# indicator_leds.net
KiCad netlist of a schematic drawn in Altium Designer
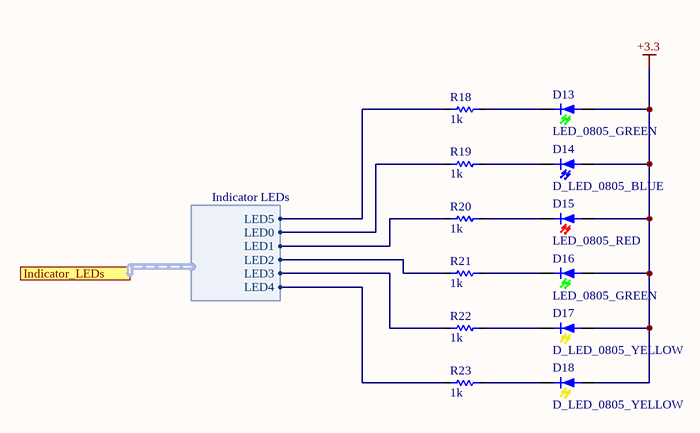
[diagram p0: indicator_leds.SchDoc]

(export (version "E")
  (design (tool "Eeschema 10.0.6"))
  (components
    (comp (ref "D13")
      (value "LED_0805_GREEN")
      (footprint "0805_LED_Green")
      (description "LED CHIPLED 570NM GREEN 0805 SMD")
      (fields
        (field (name "MANUFACTURER") "Osram Opto Semiconductors Inc")
        (field (name "SVP CREATOR") "Nate Bolyard")
      )
      (libsource (lib "University of Minnesota - Solar Vehicle Project") (part "Symbol"))
    )
    (comp (ref "D14")
      (value "D_LED_0805_BLUE")
      (footprint "0805_LED_Blue")
      (description "LED 2X1.2MM 470NM BL WTR CLR SMD")
      (fields (field (name "MANUFACTURER") "Kingbright") (field (name "SVP CREATOR") "Jonathan Nutzmann"))
      (libsource (lib "University of Minnesota - Solar Vehicle Project") (part "Symbol"))
    )
    (comp (ref "D15")
      (value "LED_0805_RED")
      (footprint "0805_LED_Red")
      (description "LED CHIPLED 645NM RED DIFF 0805")
      (fields
        (field (name "MANUFACTURER") "OSRAM Opto Semiconductors Inc")
        (field (name "SVP CREATOR") "Jonathan Nutzmann")
      )
      (libsource (lib "University of Minnesota - Solar Vehicle Project") (part "Symbol"))
    )
    (comp (ref "D16")
      (value "LED_0805_GREEN")
      (footprint "0805_LED_Green")
      (description "LED CHIPLED 570NM GREEN 0805 SMD")
      (fields
        (field (name "MANUFACTURER") "Osram Opto Semiconductors Inc")
        (field (name "SVP CREATOR") "Nate Bolyard")
      )
      (libsource (lib "University of Minnesota - Solar Vehicle Project") (part "Symbol"))
    )
    (comp (ref "D17")
      (value "D_LED_0805_YELLOW")
      (footprint "0805_LED_Yellow")
      (description "LED 595NM AMBER DIFF SMD 0805")
      (fields
        (field (name "MANUFACTURER") "Avago Technologies US Inc.")
        (field (name "SVP CREATOR") "Jonathan Nutzmann")
      )
      (libsource (lib "University of Minnesota - Solar Vehicle Project") (part "D_LED_0805_YELLOW"))
    )
    (comp (ref "D18")
      (value "D_LED_0805_YELLOW")
      (footprint "0805_LED_Yellow")
      (description "LED 595NM AMBER DIFF SMD 0805")
      (fields
        (field (name "MANUFACTURER") "Avago Technologies US Inc.")
        (field (name "SVP CREATOR") "Jonathan Nutzmann")
      )
      (libsource (lib "University of Minnesota - Solar Vehicle Project") (part "D_LED_0805_YELLOW"))
    )
    (comp (ref "R18")
      (value "1k")
      (footprint "0603_RESISTOR")
      (description "RES 1K OHM 1/16W 1% 0603 SMD")
      (fields (field (name "TOLERANCE") "1%") (field (name "POWER") "62.5mW"))
      (libsource (lib "") (part "Symbol_1"))
    )
    (comp (ref "R19")
      (value "1k")
      (footprint "0603_RESISTOR")
      (description "RES 1K OHM 1/16W 1% 0603 SMD")
      (fields (field (name "TOLERANCE") "1%") (field (name "POWER") "62.5mW"))
      (libsource (lib "") (part "Symbol_1"))
    )
    (comp (ref "R20")
      (value "1k")
      (footprint "0603_RESISTOR")
      (description "RES 1K OHM 1/16W 1% 0603 SMD")
      (fields (field (name "TOLERANCE") "1%") (field (name "POWER") "62.5mW"))
      (libsource (lib "") (part "Symbol_1"))
    )
    (comp (ref "R21")
      (value "1k")
      (footprint "0603_RESISTOR")
      (description "RES 1K OHM 1/16W 1% 0603 SMD")
      (fields (field (name "TOLERANCE") "1%") (field (name "POWER") "62.5mW"))
      (libsource (lib "") (part "Symbol_1"))
    )
    (comp (ref "R22")
      (value "1k")
      (footprint "0603_RESISTOR")
      (description "RES 1K OHM 1/16W 1% 0603 SMD")
      (fields (field (name "TOLERANCE") "1%") (field (name "POWER") "62.5mW"))
      (libsource (lib "") (part "Symbol_1"))
    )
    (comp (ref "R23")
      (value "1k")
      (footprint "0603_RESISTOR")
      (description "RES 1K OHM 1/16W 1% 0603 SMD")
      (fields (field (name "TOLERANCE") "1%") (field (name "POWER") "62.5mW"))
      (libsource (lib "") (part "Symbol_1"))
    )
  )
  (nets
    (net (code "3") (name "+3.3") (class "Default")
      (node (ref "D13") (pin "1") (pinfunction "Anode_1") (pintype "passive"))
      (node (ref "D14") (pin "1") (pinfunction "Anode_1") (pintype "passive"))
      (node (ref "D15") (pin "1") (pinfunction "Anode_1") (pintype "passive"))
      (node (ref "D16") (pin "1") (pinfunction "Anode_1") (pintype "passive"))
      (node (ref "D17") (pin "1") (pinfunction "Anode_1") (pintype "passive"))
      (node (ref "D18") (pin "1") (pinfunction "Anode_1") (pintype "passive"))
    )
    (net (code "4") (name "/LED0") (class "Default")
      (node (ref "R19") (pin "1") (pinfunction "1_1") (pintype "passive"))
    )
    (net (code "5") (name "/LED1") (class "Default")
      (node (ref "R20") (pin "1") (pinfunction "1_1") (pintype "passive"))
    )
    (net (code "6") (name "/LED2") (class "Default")
      (node (ref "R21") (pin "1") (pinfunction "1_1") (pintype "passive"))
    )
    (net (code "7") (name "/LED3") (class "Default")
      (node (ref "R22") (pin "1") (pinfunction "1_1") (pintype "passive"))
    )
    (net (code "8") (name "/LED4") (class "Default")
      (node (ref "R23") (pin "1") (pinfunction "1_1") (pintype "passive"))
    )
    (net (code "9") (name "/LED5") (class "Default")
      (node (ref "R18") (pin "1") (pinfunction "1_1") (pintype "passive"))
    )
    (net (code "11") (name "Net-(D13-Cathode)") (class "Default")
      (node (ref "D13") (pin "2") (pinfunction "Cathode_2") (pintype "passive"))
      (node (ref "R18") (pin "2") (pinfunction "2_2") (pintype "passive"))
    )
    (net (code "12") (name "Net-(D14-Cathode)") (class "Default")
      (node (ref "D14") (pin "2") (pinfunction "Cathode_2") (pintype "passive"))
      (node (ref "R19") (pin "2") (pinfunction "2_2") (pintype "passive"))
    )
    (net (code "13") (name "Net-(D15-Cathode)") (class "Default")
      (node (ref "D15") (pin "2") (pinfunction "Cathode_2") (pintype "passive"))
      (node (ref "R20") (pin "2") (pinfunction "2_2") (pintype "passive"))
    )
    (net (code "14") (name "Net-(D16-Cathode)") (class "Default")
      (node (ref "D16") (pin "2") (pinfunction "Cathode_2") (pintype "passive"))
      (node (ref "R21") (pin "2") (pinfunction "2_2") (pintype "passive"))
    )
    (net (code "15") (name "Net-(D17-Cathode)") (class "Default")
      (node (ref "D17") (pin "2") (pinfunction "Cathode_2") (pintype "passive"))
      (node (ref "R22") (pin "2") (pinfunction "2_2") (pintype "passive"))
    )
    (net (code "16") (name "Net-(D18-Cathode)") (class "Default")
      (node (ref "D18") (pin "2") (pinfunction "Cathode_2") (pintype "passive"))
      (node (ref "R23") (pin "2") (pinfunction "2_2") (pintype "passive"))
    )
  )
)
